# 01-M2_ZED-F9T_MODULE.net
KiCad netlist of a schematic drawn in Altium Designer
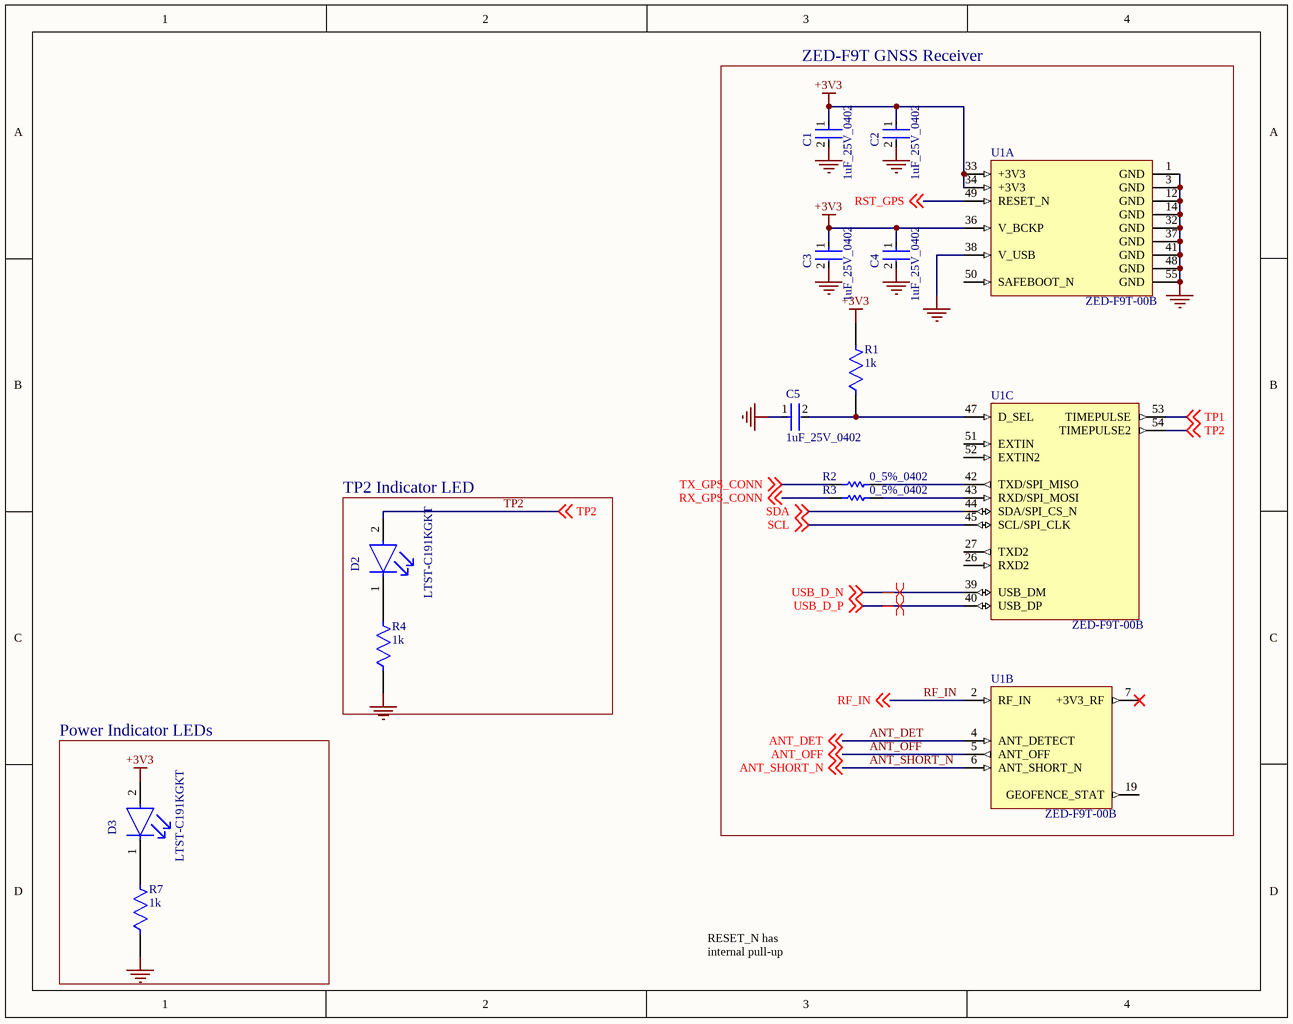
[diagram p0: 01-M2_ZED-F9T_MODULE.SchDoc]

(export (version "E")
  (design (tool "Eeschema 10.0.6"))
  (components
    (comp (ref "C1")
      (value "1uF_25V_0402")
      (footprint "FP-CL542-IPC_C")
      (description "Cap Ceramic 1uF 25V X5R ±10% SMD 0402 +85°C Paper T/R")
      (fields (field (name "TOLERANCE") "10%"))
      (libsource (lib "Altium Content Vault") (part "b4654b650e69147ec39a6b967a45e02"))
    )
    (comp (ref "C2")
      (value "1uF_25V_0402")
      (footprint "FP-CL542-IPC_C")
      (description "Cap Ceramic 1uF 25V X5R ±10% SMD 0402 +85°C Paper T/R")
      (fields (field (name "TOLERANCE") "10%"))
      (libsource (lib "Altium Content Vault") (part "b4654b650e69147ec39a6b967a45e02"))
    )
    (comp (ref "C3")
      (value "1uF_25V_0402")
      (footprint "FP-CL542-IPC_C")
      (description "Cap Ceramic 1uF 25V X5R ±10% SMD 0402 +85°C Paper T/R")
      (fields (field (name "TOLERANCE") "10%"))
      (libsource (lib "Altium Content Vault") (part "b4654b650e69147ec39a6b967a45e02"))
    )
    (comp (ref "C4")
      (value "1uF_25V_0402")
      (footprint "FP-CL542-IPC_C")
      (description "Cap Ceramic 1uF 25V X5R ±10% SMD 0402 +85°C Paper T/R")
      (fields (field (name "TOLERANCE") "10%"))
      (libsource (lib "Altium Content Vault") (part "b4654b650e69147ec39a6b967a45e02"))
    )
    (comp (ref "C5")
      (value "1uF_25V_0402")
      (footprint "FP-CL542-IPC_C")
      (description "Cap Ceramic 1uF 25V X5R ±10% SMD 0402 +85°C Paper T/R")
      (fields (field (name "TOLERANCE") "10%"))
      (libsource (lib "Altium Content Vault") (part "b4654b650e69147ec39a6b967a45e02"))
    )
    (comp (ref "D2")
      (value "LTST-C191KGKT")
      (footprint "FP-LTST-C191KGKT-MFG")
      (description "LED GREEN CLEAR SMD")
      (libsource (lib "Altium Content Vault") (part "8706943c75ba83719d021d2fdc84c58"))
    )
    (comp (ref "D3")
      (value "LTST-C191KGKT")
      (footprint "FP-LTST-C191KGKT-MFG")
      (description "LED GREEN CLEAR SMD")
      (libsource (lib "Altium Content Vault") (part "8706943c75ba83719d021d2fdc84c58"))
    )
    (comp (ref "R1")
      (value "1k")
      (footprint "FP-RMCF0402-MFG")
      (description "1kΩ ±1% 0.063W 0402 Thick Film Chip Resistor AEC-Q200 compliant")
      (fields (field (name "TOLERANCE") "1%"))
      (libsource (lib "Altium Content Vault") (part "1029c3af85768c4190bb7ad29bc67b5"))
    )
    (comp (ref "R2")
      (value "0_5%_0402")
      (footprint "RESC1005X40X25NL05T10")
      (fields (field (name "MANUFACTURER") "Panasonic") (field (name "PART NUMBER") "ERJ-U020R00X"))
      (libsource (lib "Altium Content Vault") (part "RES"))
    )
    (comp (ref "R3")
      (value "0_5%_0402")
      (footprint "RESC1005X40X25NL05T10")
      (fields (field (name "MANUFACTURER") "Panasonic") (field (name "PART NUMBER") "ERJ-U020R00X"))
      (libsource (lib "Altium Content Vault") (part "RES"))
    )
    (comp (ref "R4")
      (value "1k")
      (footprint "FP-RMCF0402-MFG")
      (description "1kΩ ±1% 0.063W 0402 Thick Film Chip Resistor AEC-Q200 compliant")
      (fields (field (name "TOLERANCE") "1%"))
      (libsource (lib "Altium Content Vault") (part "1029c3af85768c4190bb7ad29bc67b5"))
    )
    (comp (ref "R7")
      (value "1k")
      (footprint "FP-RMCF0402-MFG")
      (description "1kΩ ±1% 0.063W 0402 Thick Film Chip Resistor AEC-Q200 compliant")
      (fields (field (name "TOLERANCE") "1%"))
      (libsource (lib "Altium Content Vault") (part "1029c3af85768c4190bb7ad29bc67b5"))
    )
    (comp (ref "U1")
      (value "ZED-F9T-00B")
      (footprint "GPS_ZED-F9T")
      (description "Multi-band GNSS Receiver with Nanosecond-level Timing Accuracy")
      (fields (field (name "MANUFACTURER") "u-blox"))
      (libsource (lib "GNSS_Receiver_Library") (part "GPS_ZED-F9T"))
    )
  )
  (nets
    (net (code "1") (name "+3V3") (class "Default")
      (node (ref "C1") (pin "1") (pinfunction "1_1") (pintype "passive"))
      (node (ref "C2") (pin "1") (pinfunction "1_1") (pintype "passive"))
      (node (ref "C3") (pin "1") (pinfunction "1_1") (pintype "passive"))
      (node (ref "C4") (pin "1") (pinfunction "1_1") (pintype "passive"))
      (node (ref "D3") (pin "2") (pinfunction "A_2") (pintype "passive"))
      (node (ref "R1") (pin "2") (pinfunction "2_2") (pintype "passive"))
      (node (ref "U1") (pin "33") (pinfunction "+3V3_33") (pintype "input"))
      (node (ref "U1") (pin "34") (pinfunction "+3V3_34") (pintype "input"))
      (node (ref "U1") (pin "36") (pinfunction "V_BCKP_36") (pintype "input"))
    )
    (net (code "2") (name "ANT_DET") (class "Default")
      (node (ref "U1") (pin "4") (pinfunction "ANT_DETECT_4") (pintype "input"))
    )
    (net (code "3") (name "ANT_OFF") (class "Default")
      (node (ref "U1") (pin "5") (pinfunction "ANT_OFF_5") (pintype "output"))
    )
    (net (code "4") (name "ANT_SHORT_N") (class "Default")
      (node (ref "U1") (pin "6") (pinfunction "ANT_SHORT_N_6") (pintype "input"))
    )
    (net (code "5") (name "GND") (class "Default")
      (node (ref "C1") (pin "2") (pinfunction "2_2") (pintype "passive"))
      (node (ref "C2") (pin "2") (pinfunction "2_2") (pintype "passive"))
      (node (ref "C3") (pin "2") (pinfunction "2_2") (pintype "passive"))
      (node (ref "C4") (pin "2") (pinfunction "2_2") (pintype "passive"))
      (node (ref "C5") (pin "1") (pinfunction "1_1") (pintype "passive"))
      (node (ref "R4") (pin "1") (pinfunction "1_1") (pintype "passive"))
      (node (ref "R7") (pin "1") (pinfunction "1_1") (pintype "passive"))
      (node (ref "U1") (pin "1") (pinfunction "GND_1") (pintype "passive"))
      (node (ref "U1") (pin "12") (pinfunction "GND_12") (pintype "passive"))
      (node (ref "U1") (pin "14") (pinfunction "GND_14") (pintype "passive"))
      (node (ref "U1") (pin "3") (pinfunction "GND_3") (pintype "passive"))
      (node (ref "U1") (pin "32") (pinfunction "GND_32") (pintype "passive"))
      (node (ref "U1") (pin "37") (pinfunction "GND_37") (pintype "passive"))
      (node (ref "U1") (pin "38") (pinfunction "V_USB_38") (pintype "input"))
      (node (ref "U1") (pin "41") (pinfunction "GND_41") (pintype "passive"))
      (node (ref "U1") (pin "48") (pinfunction "GND_48") (pintype "passive"))
      (node (ref "U1") (pin "55") (pinfunction "GND_55") (pintype "passive"))
    )
    (net (code "6") (name "Net-(D2-C)") (class "Default")
      (node (ref "D2") (pin "1") (pinfunction "C_1") (pintype "passive"))
      (node (ref "R4") (pin "2") (pinfunction "2_2") (pintype "passive"))
    )
    (net (code "7") (name "Net-(D3-C)") (class "Default")
      (node (ref "D3") (pin "1") (pinfunction "C_1") (pintype "passive"))
      (node (ref "R7") (pin "2") (pinfunction "2_2") (pintype "passive"))
    )
    (net (code "8") (name "Net-(U1C-D_SEL)") (class "Default")
      (node (ref "C5") (pin "2") (pinfunction "2_2") (pintype "passive"))
      (node (ref "R1") (pin "1") (pinfunction "1_1") (pintype "passive"))
      (node (ref "U1") (pin "47") (pinfunction "D_SEL_47") (pintype "input"))
    )
    (net (code "9") (name "Net-(U1C-RXD{slash}SPI_MOSI)") (class "Default")
      (node (ref "R3") (pin "2") (pinfunction "2_2") (pintype "passive"))
      (node (ref "U1") (pin "43") (pinfunction "RXD/SPI_MOSI_43") (pintype "input"))
    )
    (net (code "10") (name "Net-(U1C-TXD{slash}SPI_MISO)") (class "Default")
      (node (ref "R2") (pin "2") (pinfunction "2_2") (pintype "passive"))
      (node (ref "U1") (pin "42") (pinfunction "TXD/SPI_MISO_42") (pintype "output"))
    )
    (net (code "11") (name "RF_IN") (class "Default")
      (node (ref "U1") (pin "2") (pinfunction "RF_IN_2") (pintype "input"))
    )
    (net (code "12") (name "RST_GPS") (class "Default")
      (node (ref "U1") (pin "49") (pinfunction "RESET_N_49") (pintype "input"))
    )
    (net (code "13") (name "RX_GPS_CONN") (class "Default")
      (node (ref "R3") (pin "1") (pinfunction "1_1") (pintype "passive"))
    )
    (net (code "14") (name "SCL") (class "Default")
      (node (ref "U1") (pin "45") (pinfunction "SCL/SPI_CLK_45") (pintype "bidirectional"))
    )
    (net (code "15") (name "SDA") (class "Default")
      (node (ref "U1") (pin "44") (pinfunction "SDA/SPI_CS_N_44") (pintype "bidirectional"))
    )
    (net (code "16") (name "TP1") (class "Default")
      (node (ref "U1") (pin "53") (pinfunction "TIMEPULSE_53") (pintype "output"))
    )
    (net (code "17") (name "TP2") (class "Default")
      (node (ref "D2") (pin "2") (pinfunction "A_2") (pintype "passive"))
      (node (ref "U1") (pin "54") (pinfunction "TIMEPULSE2_54") (pintype "output"))
    )
    (net (code "18") (name "TX_GPS_CONN") (class "Default")
      (node (ref "R2") (pin "1") (pinfunction "1_1") (pintype "passive"))
    )
    (net (code "19") (name "USB_D_N") (class "Default")
      (node (ref "U1") (pin "39") (pinfunction "USB_DM_39") (pintype "bidirectional"))
    )
    (net (code "20") (name "USB_D_P") (class "Default")
      (node (ref "U1") (pin "40") (pinfunction "USB_DP_40") (pintype "bidirectional"))
    )
    (net (code "21") (name "unconnected-(U1A-SAFEBOOT_N-Pad50)") (class "Default")
      (node (ref "U1") (pin "50") (pinfunction "SAFEBOOT_N_50") (pintype "input"))
    )
    (net (code "22") (name "unconnected-(U1B-GEOFENCE_STAT-Pad19)") (class "Default")
      (node (ref "U1") (pin "19") (pinfunction "GEOFENCE_STAT_19") (pintype "output"))
    )
    (net (code "23") (name "unconnected-(U1B-VCC_RF-Pad7)") (class "Default")
      (node (ref "U1") (pin "7") (pinfunction "VCC_RF_7") (pintype "output+no_connect"))
    )
    (net (code "24") (name "unconnected-(U1C-EXTIN-Pad51)") (class "Default")
      (node (ref "U1") (pin "51") (pinfunction "EXTIN_51") (pintype "input"))
    )
    (net (code "25") (name "unconnected-(U1C-EXTIN2-Pad52)") (class "Default")
      (node (ref "U1") (pin "52") (pinfunction "EXTIN2_52") (pintype "input"))
    )
    (net (code "26") (name "unconnected-(U1C-RXD2-Pad26)") (class "Default")
      (node (ref "U1") (pin "26") (pinfunction "RXD2_26") (pintype "input"))
    )
    (net (code "27") (name "unconnected-(U1C-TXD2-Pad27)") (class "Default")
      (node (ref "U1") (pin "27") (pinfunction "TXD2_27") (pintype "output"))
    )
  )
)
